# SCH_GroeiAcademie-Arduino_Uno_R3-R4_Shie.net
KiCad netlist of a schematic drawn in EasyEDA
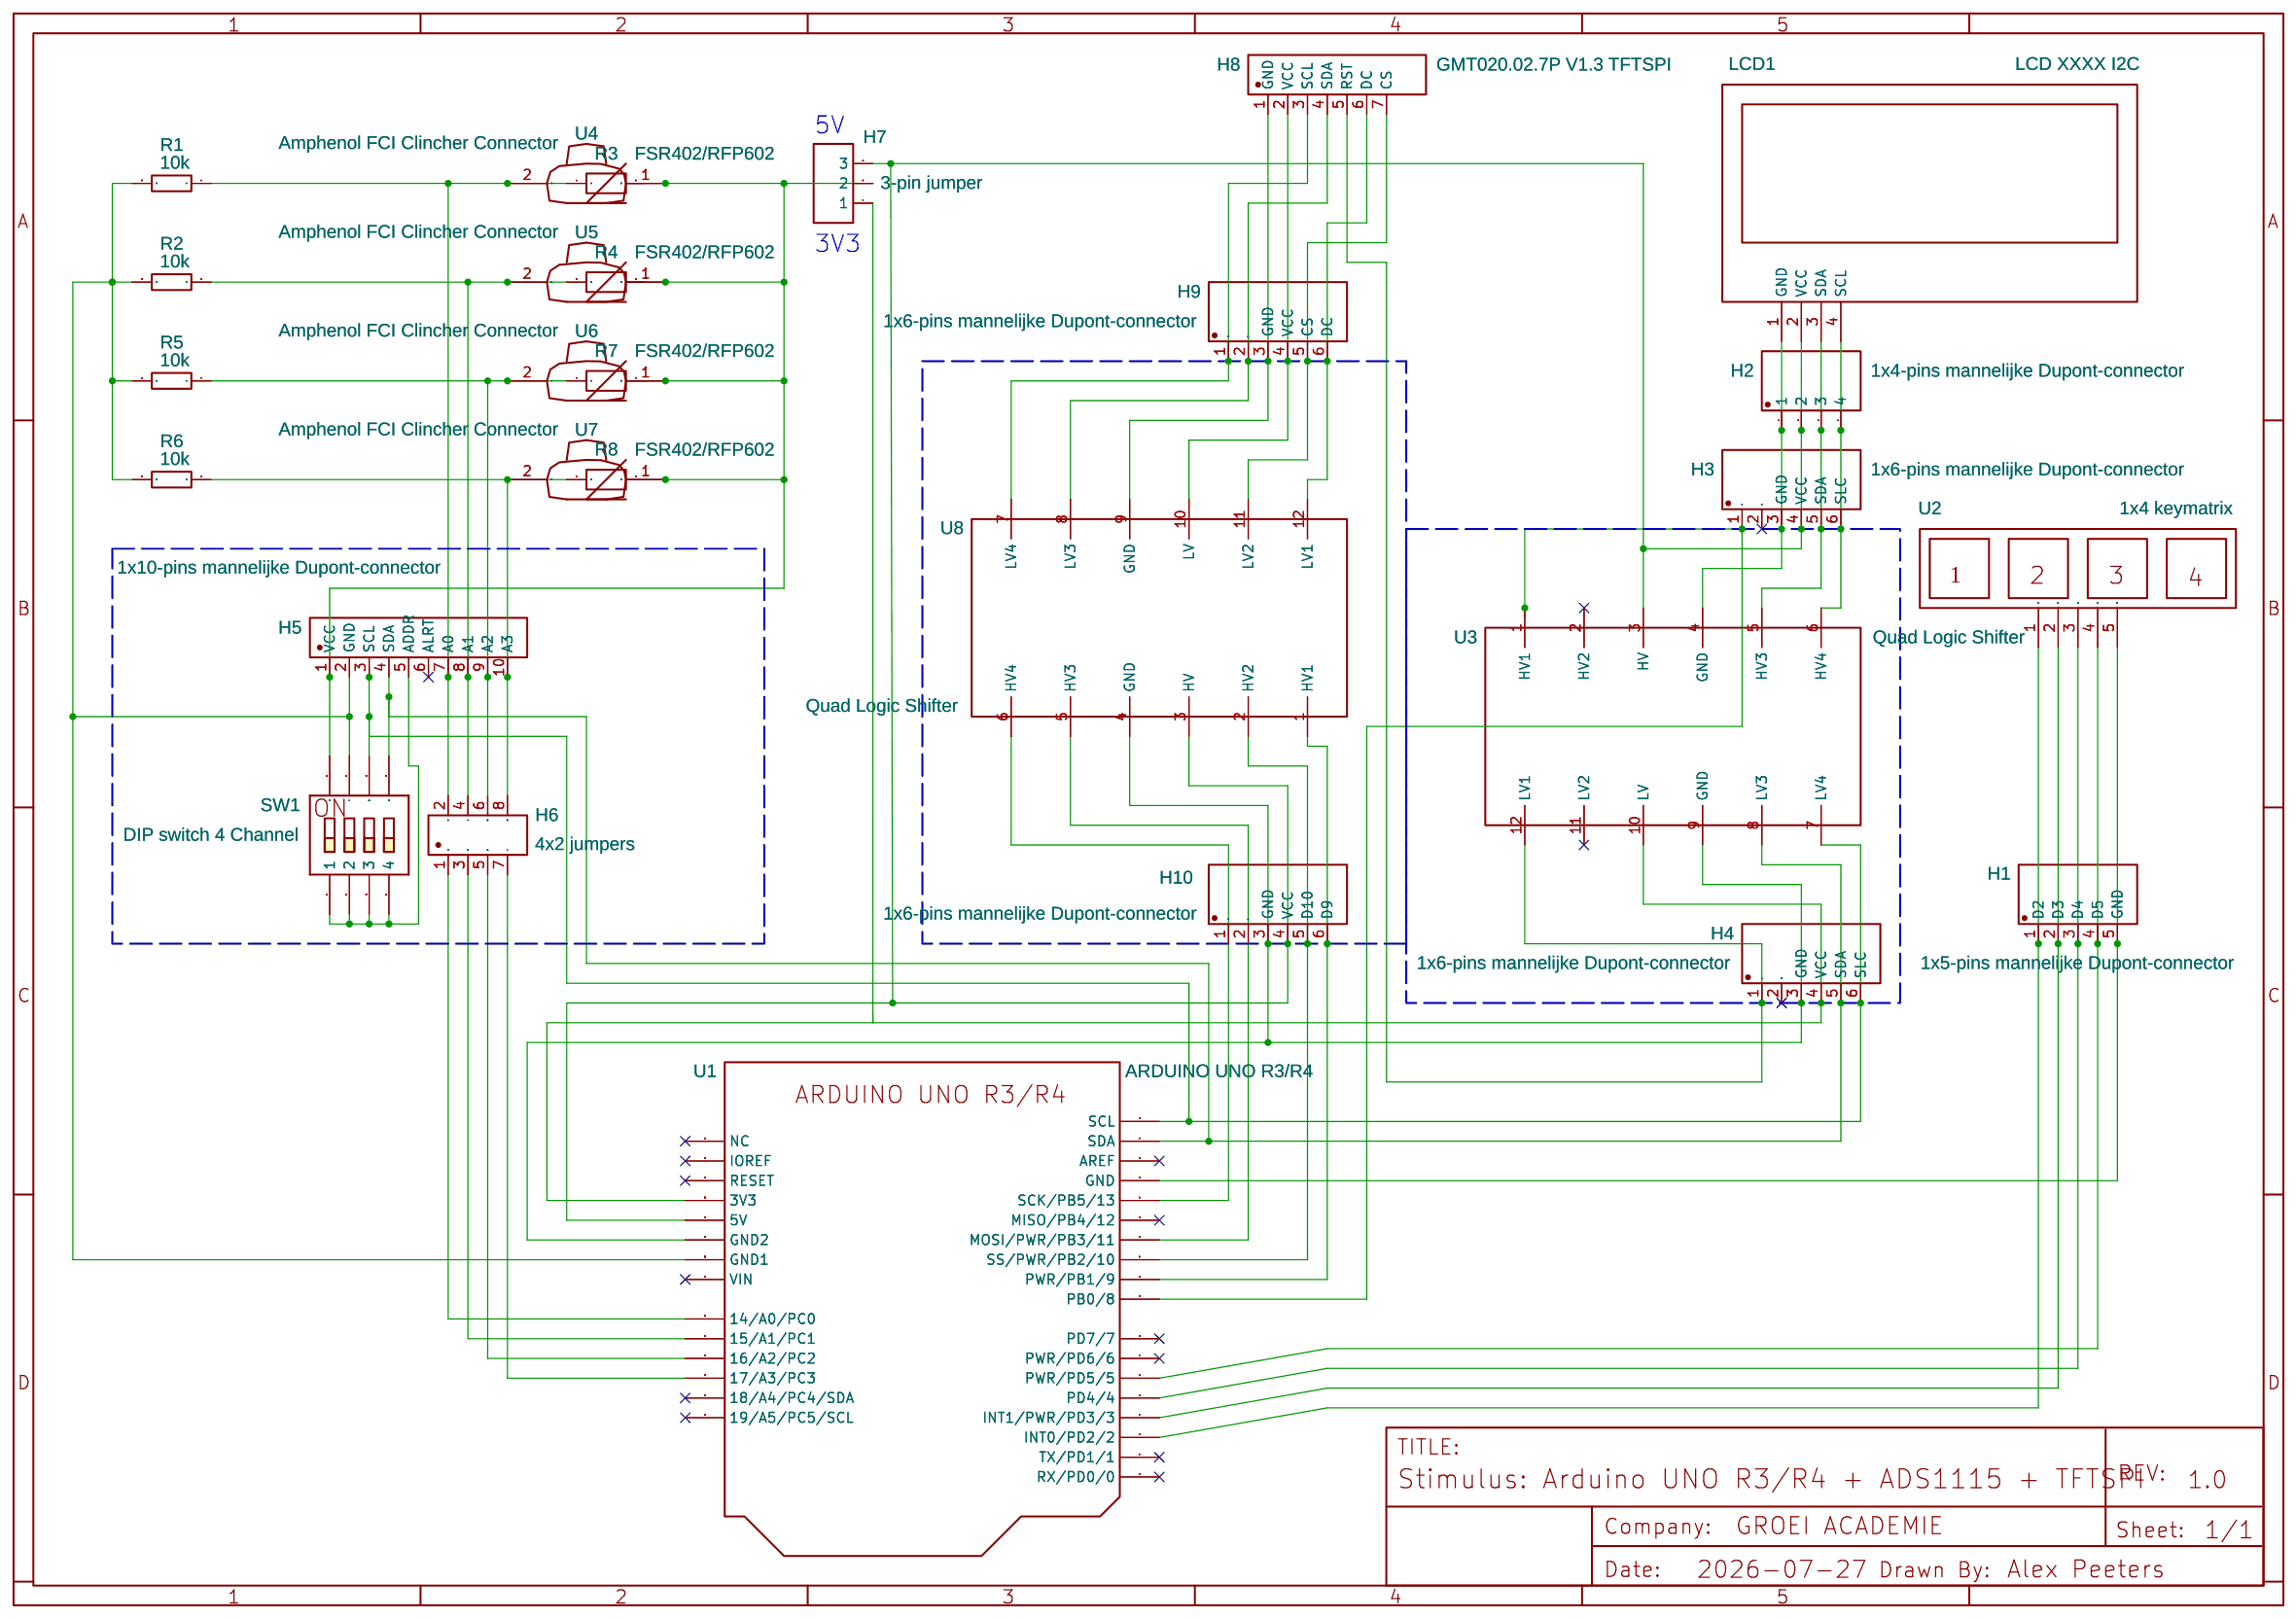
[diagram p0: schematic sheet]

(export (version "E")
  (design (tool "Eeschema 10.0.6"))
  (components
    (comp (ref "H1")
      (value "1x5-pins mannelijke Dupont-connector")
      (fields (field (name "Manufacturer Part") "B-2100S05P-A110") (field (name "Manufacturer") "Ckmtw(灿科盟)"))
      (libsource (lib "") (part "210S-1*5P L=11.6MMGold-plated black"))
    )
    (comp (ref "H2")
      (value "1x4-pins mannelijke Dupont-connector")
      (fields (field (name "Manufacturer Part") "B-2100S04P-A110") (field (name "Manufacturer") "Ckmtw(灿科盟)"))
      (libsource (lib "") (part "Header-Male-2.54_1x4"))
    )
    (comp (ref "H3")
      (value "1x6-pins mannelijke Dupont-connector")
      (fields (field (name "Manufacturer Part") "B-2100S06P-A110") (field (name "Manufacturer") "Ckmtw(灿科盟)"))
      (libsource (lib "") (part "210S-1*6P L=11.6MMGold-plated black"))
    )
    (comp (ref "H4")
      (value "1x6-pins mannelijke Dupont-connector")
      (fields (field (name "Manufacturer Part") "B-2100S06P-A110") (field (name "Manufacturer") "Ckmtw(灿科盟)"))
      (libsource (lib "") (part "210S-1*6P L=11.6MMGold-plated black"))
    )
    (comp (ref "H5")
      (value "1x10-pins mannelijke Dupont-connector")
      (fields (field (name "Manufacturer Part") "2.54-1*10") (field (name "Manufacturer") "ZHOURI(洲日)"))
      (libsource (lib "") (part "2.54-1*10"))
    )
    (comp (ref "H6")
      (value "4x2 jumpers")
      (fields (field (name "Manufacturer Part") "2.54-2*4P立贴针") (field (name "Manufacturer") "BOOMELE(博穆精密)"))
      (libsource (lib "") (part "2.54-2*4P立贴针"))
    )
    (comp (ref "H7") (value "3-pin jumper") (libsource (lib "") (part "HDR-F-2.54_1x3")))
    (comp (ref "H8")
      (value "GMT020.02.7P V1.3 TFTSPI")
      (fields (field (name "Manufacturer Part") "HDR-M-L12-3+4-1x8P-2.54"))
      (libsource (lib "") (part "PZ254R-11-08P"))
    )
    (comp (ref "H9")
      (value "1x6-pins mannelijke Dupont-connector")
      (fields (field (name "Manufacturer Part") "B-2100S06P-A110") (field (name "Manufacturer") "Ckmtw(灿科盟)"))
      (libsource (lib "") (part "210S-1*6P L=11.6MMGold-plated black_1"))
    )
    (comp (ref "H10")
      (value "1x6-pins mannelijke Dupont-connector")
      (fields (field (name "Manufacturer Part") "B-2100S06P-A110") (field (name "Manufacturer") "Ckmtw(灿科盟)"))
      (libsource (lib "") (part "210S-1*6P L=11.6MMGold-plated black_2"))
    )
    (comp (ref "LCD1") (value "LCD XXXX I2C") (libsource (lib "") (part "I2CLCD16X2_N")))
    (comp (ref "R1")
      (value "10k")
      (fields (field (name "Manufacturer") "Made in China"))
      (libsource (lib "") (part "330Ω (331) ±5%"))
    )
    (comp (ref "R2")
      (value "10k")
      (fields (field (name "Manufacturer") "Made in China"))
      (libsource (lib "") (part "330Ω (331) ±5%"))
    )
    (comp (ref "R3") (value "FSR402/RFP602") (libsource (lib "") (part "FSR402-OPCION1")))
    (comp (ref "R4") (value "FSR402/RFP602") (libsource (lib "") (part "FSR402-OPCION1")))
    (comp (ref "R5")
      (value "10k")
      (fields (field (name "Manufacturer") "Made in China"))
      (libsource (lib "") (part "330Ω (331) ±5%"))
    )
    (comp (ref "R6")
      (value "10k")
      (fields (field (name "Manufacturer") "Made in China"))
      (libsource (lib "") (part "330Ω (331) ±5%"))
    )
    (comp (ref "R7") (value "FSR402/RFP602") (libsource (lib "") (part "FSR402-OPCION1")))
    (comp (ref "R8") (value "FSR402/RFP602") (libsource (lib "") (part "FSR402-OPCION1")))
    (comp (ref "SW1")
      (value "DIP switch 4 Channel")
      (fields
        (field (name "Manufacturer Part") "DIP switch,Dip Switch,DSWB04LHGET")
        (field (name "Manufacturer") "KE")
      )
      (libsource (lib "") (part "DIP switch 4 Channel"))
    )
    (comp (ref "U1") (value "ARDUINO UNO R3/R4") (libsource (lib "") (part "ARDUINO UNO r3")))
    (comp (ref "U2") (value "1x4 keymatrix") (libsource (lib "") (part "Клавиатура 4*4")))
    (comp (ref "U3") (value "Quad Logic Shifter") (libsource (lib "") (part "Quad Logic Shifter")))
    (comp (ref "U4")
      (value "Amphenol FCI Clincher Connector")
      (fields (field (name "Manufacturer Part") "AT04-2P-BM02") (field (name "Manufacturer") "Amphenol"))
      (libsource (lib "") (part "AT04-2P"))
    )
    (comp (ref "U5")
      (value "Amphenol FCI Clincher Connector")
      (fields (field (name "Manufacturer Part") "AT04-2P-BM02") (field (name "Manufacturer") "Amphenol"))
      (libsource (lib "") (part "AT04-2P"))
    )
    (comp (ref "U6")
      (value "Amphenol FCI Clincher Connector")
      (fields (field (name "Manufacturer Part") "AT04-2P-BM02") (field (name "Manufacturer") "Amphenol"))
      (libsource (lib "") (part "AT04-2P"))
    )
    (comp (ref "U7")
      (value "Amphenol FCI Clincher Connector")
      (fields (field (name "Manufacturer Part") "AT04-2P-BM02") (field (name "Manufacturer") "Amphenol"))
      (libsource (lib "") (part "AT04-2P"))
    )
    (comp (ref "U8") (value "Quad Logic Shifter") (libsource (lib "") (part "Quad Logic Shifter_1")))
  )
  (nets
    (net (code "1") (name "Net-(H1-D2)") (class "Default")
      (node (ref "H1") (pin "1") (pinfunction "D2_1") (pintype "unspecified"))
      (node (ref "U1") (pin "3") (pinfunction "INT0/PD2/2_3") (pintype "unspecified"))
      (node (ref "U2") (pin "1") (pinfunction "C1_1") (pintype "unspecified"))
    )
    (net (code "2") (name "Net-(H1-D3)") (class "Default")
      (node (ref "H1") (pin "2") (pinfunction "D3_2") (pintype "unspecified"))
      (node (ref "U1") (pin "4") (pinfunction "INT1/PWR/PD3/3_4") (pintype "unspecified"))
      (node (ref "U2") (pin "2") (pinfunction "C2_2") (pintype "unspecified"))
    )
    (net (code "3") (name "Net-(H1-D4)") (class "Default")
      (node (ref "H1") (pin "3") (pinfunction "D4_3") (pintype "unspecified"))
      (node (ref "U1") (pin "5") (pinfunction "PD4/4_5") (pintype "unspecified"))
      (node (ref "U2") (pin "3") (pinfunction "C3_3") (pintype "unspecified"))
    )
    (net (code "4") (name "Net-(H1-D5)") (class "Default")
      (node (ref "H1") (pin "4") (pinfunction "D5_4") (pintype "unspecified"))
      (node (ref "U1") (pin "6") (pinfunction "PWR/PD5/5_6") (pintype "unspecified"))
      (node (ref "U2") (pin "4") (pinfunction "R1_4") (pintype "unspecified"))
    )
    (net (code "5") (name "Net-(H1-GND)") (class "Default")
      (node (ref "H1") (pin "5") (pinfunction "GND_5") (pintype "unspecified"))
      (node (ref "U1") (pin "15") (pinfunction "GND_15") (pintype "passive"))
      (node (ref "U2") (pin "5") (pinfunction "R2_5") (pintype "unspecified"))
    )
    (net (code "6") (name "Net-(H3-GND)") (class "Default")
      (node (ref "H2") (pin "1") (pinfunction "1_1") (pintype "unspecified"))
      (node (ref "H3") (pin "3") (pinfunction "GND_3") (pintype "unspecified"))
      (node (ref "LCD1") (pin "1") (pinfunction "GND_1") (pintype "unspecified"))
      (node (ref "U3") (pin "4") (pinfunction "GND_4") (pintype "unspecified"))
    )
    (net (code "7") (name "Net-(H3-SDA)") (class "Default")
      (node (ref "H2") (pin "3") (pinfunction "3_3") (pintype "unspecified"))
      (node (ref "H3") (pin "5") (pinfunction "SDA_5") (pintype "unspecified"))
      (node (ref "LCD1") (pin "3") (pinfunction "SDA_3") (pintype "unspecified"))
      (node (ref "U3") (pin "5") (pinfunction "HV3_5") (pintype "unspecified"))
    )
    (net (code "8") (name "Net-(H3-SLC)") (class "Default")
      (node (ref "H2") (pin "4") (pinfunction "4_4") (pintype "unspecified"))
      (node (ref "H3") (pin "6") (pinfunction "SLC_6") (pintype "unspecified"))
      (node (ref "LCD1") (pin "4") (pinfunction "SCL_4") (pintype "unspecified"))
      (node (ref "U3") (pin "6") (pinfunction "HV4_6") (pintype "unspecified"))
    )
    (net (code "9") (name "Net-(H4-SDA)") (class "Default")
      (node (ref "H4") (pin "5") (pinfunction "SDA_5") (pintype "unspecified"))
      (node (ref "H5") (pin "4") (pinfunction "SDA_4") (pintype "unspecified"))
      (node (ref "SW1") (pin "4I") (pinfunction "5_4I") (pintype "input"))
      (node (ref "U1") (pin "17") (pinfunction "SDA_17") (pintype "unspecified"))
      (node (ref "U3") (pin "8") (pinfunction "LV3_8") (pintype "unspecified"))
    )
    (net (code "10") (name "Net-(H4-SLC)") (class "Default")
      (node (ref "H4") (pin "6") (pinfunction "SLC_6") (pintype "unspecified"))
      (node (ref "H5") (pin "3") (pinfunction "SCL_3") (pintype "unspecified"))
      (node (ref "SW1") (pin "3I") (pinfunction "6_3I") (pintype "input"))
      (node (ref "U1") (pin "18") (pinfunction "SCL_18") (pintype "unspecified"))
      (node (ref "U3") (pin "7") (pinfunction "LV4_7") (pintype "unspecified"))
    )
    (net (code "11") (name "Net-(H4-VCC)") (class "Default")
      (node (ref "H4") (pin "4") (pinfunction "VCC_4") (pintype "unspecified"))
      (node (ref "U1") (pin "29") (pinfunction "3V3_29") (pintype "passive"))
      (node (ref "U3") (pin "10") (pinfunction "LV_10") (pintype "unspecified"))
    )
    (net (code "12") (name "Net-(H5-A0)") (class "Default")
      (node (ref "H5") (pin "7") (pinfunction "A0_7") (pintype "unspecified"))
      (node (ref "H6") (pin "2") (pinfunction "2_2") (pintype "unspecified"))
      (node (ref "R1") (pin "1") (pinfunction "1_1") (pintype "unspecified"))
      (node (ref "R3") (pin "1") (pinfunction "1_1") (pintype "unspecified"))
      (node (ref "U4") (pin "2") (pinfunction "2_2") (pintype "unspecified"))
    )
    (net (code "13") (name "Net-(H5-A1)") (class "Default")
      (node (ref "H5") (pin "8") (pinfunction "A1_8") (pintype "unspecified"))
      (node (ref "H6") (pin "4") (pinfunction "4_4") (pintype "unspecified"))
      (node (ref "R2") (pin "1") (pinfunction "1_1") (pintype "unspecified"))
      (node (ref "R4") (pin "1") (pinfunction "1_1") (pintype "unspecified"))
      (node (ref "U5") (pin "2") (pinfunction "2_2") (pintype "unspecified"))
    )
    (net (code "14") (name "Net-(H5-A2)") (class "Default")
      (node (ref "H5") (pin "9") (pinfunction "A2_9") (pintype "unspecified"))
      (node (ref "H6") (pin "6") (pinfunction "6_6") (pintype "unspecified"))
      (node (ref "R5") (pin "1") (pinfunction "1_1") (pintype "unspecified"))
      (node (ref "R7") (pin "1") (pinfunction "1_1") (pintype "unspecified"))
      (node (ref "U6") (pin "2") (pinfunction "2_2") (pintype "unspecified"))
    )
    (net (code "15") (name "Net-(H5-A3)") (class "Default")
      (node (ref "H5") (pin "10") (pinfunction "A3_10") (pintype "unspecified"))
      (node (ref "H6") (pin "8") (pinfunction "8_8") (pintype "unspecified"))
      (node (ref "R6") (pin "1") (pinfunction "1_1") (pintype "unspecified"))
      (node (ref "R8") (pin "1") (pinfunction "1_1") (pintype "unspecified"))
      (node (ref "U7") (pin "2") (pinfunction "2_2") (pintype "unspecified"))
    )
    (net (code "16") (name "Net-(H5-ADDR)") (class "Default")
      (node (ref "H5") (pin "5") (pinfunction "ADDR_5") (pintype "unspecified"))
      (node (ref "SW1") (pin "1O") (pinfunction "1_1O") (pintype "input"))
      (node (ref "SW1") (pin "2O") (pinfunction "2_2O") (pintype "input"))
      (node (ref "SW1") (pin "3O") (pinfunction "3_3O") (pintype "input"))
      (node (ref "SW1") (pin "4O") (pinfunction "4_4O") (pintype "input"))
    )
    (net (code "17") (name "Net-(H5-GND)") (class "Default")
      (node (ref "H5") (pin "2") (pinfunction "GND_2") (pintype "unspecified"))
      (node (ref "R1") (pin "2") (pinfunction "2_2") (pintype "unspecified"))
      (node (ref "R2") (pin "2") (pinfunction "2_2") (pintype "unspecified"))
      (node (ref "R5") (pin "2") (pinfunction "2_2") (pintype "unspecified"))
      (node (ref "R6") (pin "2") (pinfunction "2_2") (pintype "unspecified"))
      (node (ref "SW1") (pin "2I") (pinfunction "7_2I") (pintype "input"))
      (node (ref "U1") (pin "26") (pinfunction "GND1_26") (pintype "passive"))
    )
    (net (code "18") (name "Net-(H5-VCC)") (class "Default")
      (node (ref "H5") (pin "1") (pinfunction "VCC_1") (pintype "unspecified"))
      (node (ref "H7") (pin "2") (pinfunction "2_2") (pintype "input"))
      (node (ref "R3") (pin "2") (pinfunction "2_2") (pintype "unspecified"))
      (node (ref "R4") (pin "2") (pinfunction "2_2") (pintype "unspecified"))
      (node (ref "R7") (pin "2") (pinfunction "2_2") (pintype "unspecified"))
      (node (ref "R8") (pin "2") (pinfunction "2_2") (pintype "unspecified"))
      (node (ref "SW1") (pin "1I") (pinfunction "8_1I") (pintype "input"))
      (node (ref "U4") (pin "1") (pinfunction "1_1") (pintype "unspecified"))
      (node (ref "U5") (pin "1") (pinfunction "1_1") (pintype "unspecified"))
      (node (ref "U6") (pin "1") (pinfunction "1_1") (pintype "unspecified"))
      (node (ref "U7") (pin "1") (pinfunction "1_1") (pintype "unspecified"))
    )
    (net (code "19") (name "Net-(H8-CS)") (class "Default")
      (node (ref "H8") (pin "7") (pinfunction "CS_7") (pintype "unspecified"))
      (node (ref "H9") (pin "5") (pinfunction "CS_5") (pintype "unspecified"))
      (node (ref "U8") (pin "11") (pinfunction "LV2_11") (pintype "unspecified"))
    )
    (net (code "20") (name "Net-(H8-DC)") (class "Default")
      (node (ref "H8") (pin "6") (pinfunction "DC_6") (pintype "unspecified"))
      (node (ref "H9") (pin "6") (pinfunction "DC_6") (pintype "unspecified"))
      (node (ref "U8") (pin "12") (pinfunction "LV1_12") (pintype "unspecified"))
    )
    (net (code "21") (name "Net-(H8-GND)") (class "Default")
      (node (ref "H8") (pin "1") (pinfunction "GND_1") (pintype "unspecified"))
      (node (ref "H9") (pin "3") (pinfunction "GND_3") (pintype "unspecified"))
      (node (ref "U8") (pin "9") (pinfunction "GND_9") (pintype "unspecified"))
    )
    (net (code "22") (name "Net-(H8-RST)") (class "Default")
      (node (ref "H4") (pin "1") (pinfunction "1_1") (pintype "unspecified"))
      (node (ref "H8") (pin "5") (pinfunction "RST_5") (pintype "unspecified"))
      (node (ref "U3") (pin "12") (pinfunction "LV1_12") (pintype "unspecified"))
    )
    (net (code "23") (name "Net-(H8-SCL)") (class "Default")
      (node (ref "H8") (pin "3") (pinfunction "SCL_3") (pintype "unspecified"))
      (node (ref "H9") (pin "1") (pinfunction "1_1") (pintype "unspecified"))
      (node (ref "U8") (pin "7") (pinfunction "LV4_7") (pintype "unspecified"))
    )
    (net (code "24") (name "Net-(H8-SDA)") (class "Default")
      (node (ref "H8") (pin "4") (pinfunction "SDA_4") (pintype "unspecified"))
      (node (ref "H9") (pin "2") (pinfunction "2_2") (pintype "unspecified"))
      (node (ref "U8") (pin "8") (pinfunction "LV3_8") (pintype "unspecified"))
    )
    (net (code "25") (name "Net-(H8-VCC)") (class "Default")
      (node (ref "H8") (pin "2") (pinfunction "VCC_2") (pintype "unspecified"))
      (node (ref "H9") (pin "4") (pinfunction "VCC_4") (pintype "unspecified"))
      (node (ref "U8") (pin "10") (pinfunction "LV_10") (pintype "unspecified"))
    )
    (net (code "26") (name "Net-(H10-D9)") (class "Default")
      (node (ref "H10") (pin "6") (pinfunction "D9_6") (pintype "unspecified"))
      (node (ref "U1") (pin "10") (pinfunction "PWR/PB1/9_10") (pintype "unspecified"))
      (node (ref "U8") (pin "1") (pinfunction "HV1_1") (pintype "unspecified"))
    )
    (net (code "27") (name "Net-(H10-D10)") (class "Default")
      (node (ref "H10") (pin "5") (pinfunction "D10_5") (pintype "unspecified"))
      (node (ref "U1") (pin "11") (pinfunction "SS/PWR/PB2/10_11") (pintype "unspecified"))
      (node (ref "U8") (pin "2") (pinfunction "HV2_2") (pintype "unspecified"))
    )
    (net (code "28") (name "Net-(H10-GND)") (class "Default")
      (node (ref "H10") (pin "3") (pinfunction "GND_3") (pintype "unspecified"))
      (node (ref "H4") (pin "3") (pinfunction "GND_3") (pintype "unspecified"))
      (node (ref "U1") (pin "27") (pinfunction "GND2_27") (pintype "passive"))
      (node (ref "U3") (pin "9") (pinfunction "GND_9") (pintype "unspecified"))
      (node (ref "U8") (pin "4") (pinfunction "GND_4") (pintype "unspecified"))
    )
    (net (code "29") (name "Net-(H10-VCC)") (class "Default")
      (node (ref "H10") (pin "4") (pinfunction "VCC_4") (pintype "unspecified"))
      (node (ref "H2") (pin "2") (pinfunction "2_2") (pintype "unspecified"))
      (node (ref "H3") (pin "4") (pinfunction "VCC_4") (pintype "unspecified"))
      (node (ref "H7") (pin "3") (pinfunction "3_3") (pintype "input"))
      (node (ref "LCD1") (pin "2") (pinfunction "VCC_2") (pintype "unspecified"))
      (node (ref "U1") (pin "28") (pinfunction "5V_28") (pintype "passive"))
      (node (ref "U3") (pin "3") (pinfunction "HV_3") (pintype "unspecified"))
      (node (ref "U8") (pin "3") (pinfunction "HV_3") (pintype "unspecified"))
    )
    (net (code "30") (name "Net-(U1-14{slash}A0{slash}PC0)") (class "Default")
      (node (ref "H6") (pin "1") (pinfunction "1_1") (pintype "unspecified"))
      (node (ref "U1") (pin "24") (pinfunction "14/A0/PC0_24") (pintype "unspecified"))
    )
    (net (code "31") (name "Net-(U1-15{slash}A1{slash}PC1)") (class "Default")
      (node (ref "H6") (pin "3") (pinfunction "3_3") (pintype "unspecified"))
      (node (ref "U1") (pin "23") (pinfunction "15/A1/PC1_23") (pintype "unspecified"))
    )
    (net (code "32") (name "Net-(U1-16{slash}A2{slash}PC2)") (class "Default")
      (node (ref "H6") (pin "5") (pinfunction "5_5") (pintype "unspecified"))
      (node (ref "U1") (pin "22") (pinfunction "16/A2/PC2_22") (pintype "unspecified"))
    )
    (net (code "33") (name "Net-(U1-17{slash}A3{slash}PC3)") (class "Default")
      (node (ref "H6") (pin "7") (pinfunction "7_7") (pintype "unspecified"))
      (node (ref "U1") (pin "21") (pinfunction "17/A3/PC3_21") (pintype "unspecified"))
    )
    (net (code "34") (name "Net-(U1-MOSI{slash}PWR{slash}PB3{slash}11)") (class "Default")
      (node (ref "H10") (pin "2") (pinfunction "2_2") (pintype "unspecified"))
      (node (ref "U1") (pin "12") (pinfunction "MOSI/PWR/PB3/11_12") (pintype "unspecified"))
    )
    (net (code "35") (name "Net-(U1-PB0{slash}8)") (class "Default")
      (node (ref "H3") (pin "1") (pinfunction "1_1") (pintype "unspecified"))
      (node (ref "U1") (pin "9") (pinfunction "PB0/8_9") (pintype "unspecified"))
      (node (ref "U3") (pin "1") (pinfunction "HV1_1") (pintype "unspecified"))
    )
    (net (code "36") (name "Net-(U1-SCK{slash}PB5{slash}13)") (class "Default")
      (node (ref "H10") (pin "1") (pinfunction "1_1") (pintype "unspecified"))
      (node (ref "U1") (pin "14") (pinfunction "SCK/PB5/13_14") (pintype "unspecified"))
    )
    (net (code "37") (name "unconnected-(H3-Pad2)") (class "Default")
      (node (ref "H3") (pin "2") (pinfunction "2_2") (pintype "unspecified+no_connect"))
    )
    (net (code "38") (name "unconnected-(H4-Pad2)") (class "Default")
      (node (ref "H4") (pin "2") (pinfunction "2_2") (pintype "unspecified+no_connect"))
    )
    (net (code "39") (name "unconnected-(H5-ALRT-Pad6)") (class "Default")
      (node (ref "H5") (pin "6") (pinfunction "ALRT_6") (pintype "unspecified+no_connect"))
    )
    (net (code "40") (name "unconnected-(H7-Pad1)") (class "Default")
      (node (ref "H7") (pin "1") (pinfunction "1_1") (pintype "input"))
    )
    (net (code "41") (name "unconnected-(U1-18{slash}A4{slash}PC4{slash}SDA-Pad20)") (class "Default")
      (node (ref "U1") (pin "20") (pinfunction "18/A4/PC4/SDA_20") (pintype "unspecified+no_connect"))
    )
    (net (code "42") (name "unconnected-(U1-19{slash}A5{slash}PC5{slash}SCL-Pad19)") (class "Default")
      (node (ref "U1") (pin "19") (pinfunction "19/A5/PC5/SCL_19") (pintype "unspecified+no_connect"))
    )
    (net (code "43") (name "unconnected-(U1-AREF-Pad16)") (class "Default")
      (node (ref "U1") (pin "16") (pinfunction "AREF_16") (pintype "unspecified+no_connect"))
    )
    (net (code "44") (name "unconnected-(U1-IOREF-Pad31)") (class "Default")
      (node (ref "U1") (pin "31") (pinfunction "IOREF_31") (pintype "unspecified+no_connect"))
    )
    (net (code "45") (name "unconnected-(U1-MISO{slash}PB4{slash}12-Pad13)") (class "Default")
      (node (ref "U1") (pin "13") (pinfunction "MISO/PB4/12_13") (pintype "unspecified+no_connect"))
    )
    (net (code "46") (name "unconnected-(U1-NC-Pad32)") (class "Default")
      (node (ref "U1") (pin "32") (pinfunction "NC_32") (pintype "unspecified+no_connect"))
    )
    (net (code "47") (name "unconnected-(U1-PD7{slash}7-Pad8)") (class "Default")
      (node (ref "U1") (pin "8") (pinfunction "PD7/7_8") (pintype "unspecified+no_connect"))
    )
    (net (code "48") (name "unconnected-(U1-PWR{slash}PD6{slash}6-Pad7)") (class "Default")
      (node (ref "U1") (pin "7") (pinfunction "PWR/PD6/6_7") (pintype "unspecified+no_connect"))
    )
    (net (code "49") (name "unconnected-(U1-RESET-Pad30)") (class "Default")
      (node (ref "U1") (pin "30") (pinfunction "RESET_30") (pintype "unspecified+no_connect"))
    )
    (net (code "50") (name "unconnected-(U1-RX{slash}PD0{slash}0-Pad1)") (class "Default")
      (node (ref "U1") (pin "1") (pinfunction "RX/PD0/0_1") (pintype "unspecified+no_connect"))
    )
    (net (code "51") (name "unconnected-(U1-TX{slash}PD1{slash}1-Pad2)") (class "Default")
      (node (ref "U1") (pin "2") (pinfunction "TX/PD1/1_2") (pintype "unspecified+no_connect"))
    )
    (net (code "52") (name "unconnected-(U1-VIN-Pad25)") (class "Default")
      (node (ref "U1") (pin "25") (pinfunction "VIN_25") (pintype "passive+no_connect"))
    )
    (net (code "53") (name "unconnected-(U3-HV2-Pad2)") (class "Default")
      (node (ref "U3") (pin "2") (pinfunction "HV2_2") (pintype "unspecified+no_connect"))
    )
    (net (code "54") (name "unconnected-(U3-LV2-Pad11)") (class "Default")
      (node (ref "U3") (pin "11") (pinfunction "LV2_11") (pintype "unspecified+no_connect"))
    )
    (net (code "55") (name "unconnected-(U8-HV3-Pad5)") (class "Default")
      (node (ref "U8") (pin "5") (pinfunction "HV3_5") (pintype "unspecified"))
    )
    (net (code "56") (name "unconnected-(U8-HV4-Pad6)") (class "Default")
      (node (ref "U8") (pin "6") (pinfunction "HV4_6") (pintype "unspecified"))
    )
  )
)
